# stepper_driver.net
KiCad netlist of a schematic drawn in EAGLE
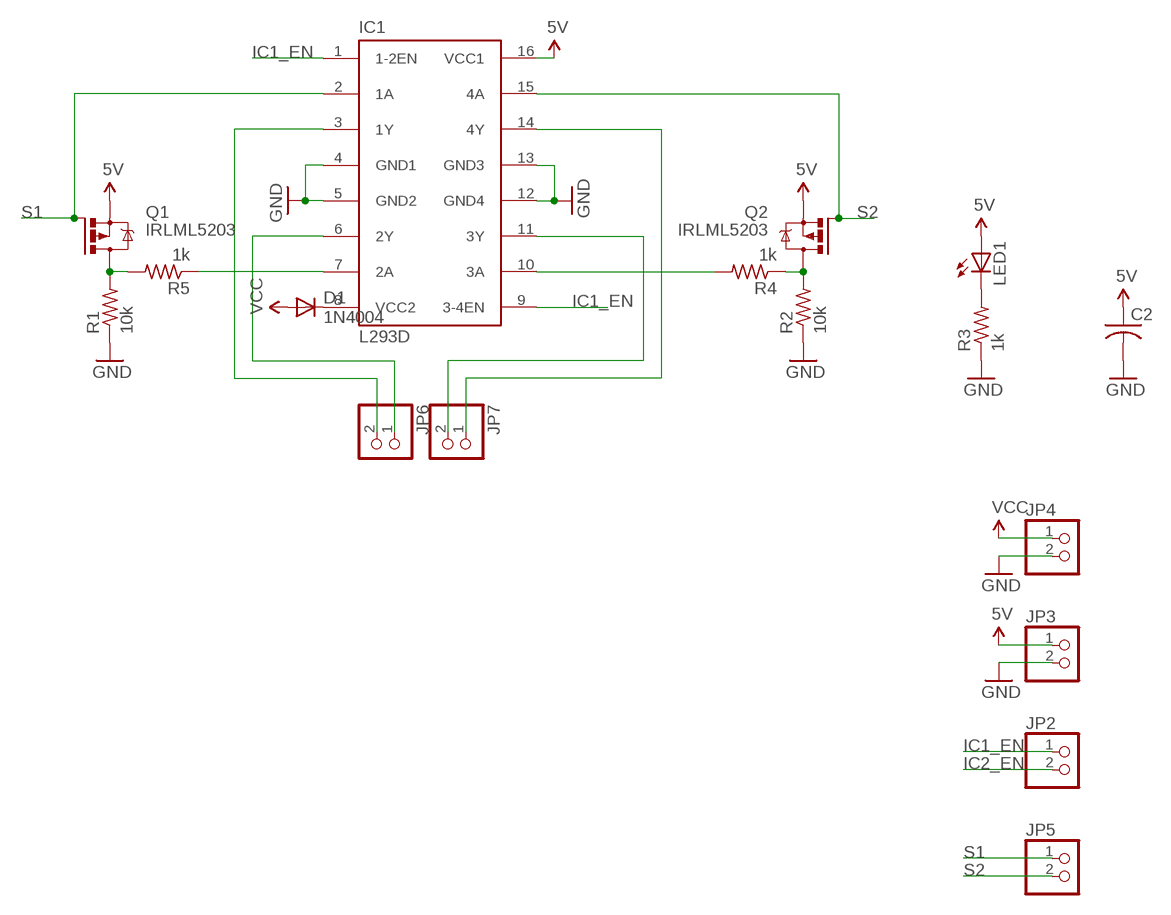
[diagram p0: schematic, sheet 1]

(export (version "E")
  (design (tool "Eeschema 10.0.6"))
  (components
    (comp (ref "C2")
      (value "C-USC1206")
      (footprint "eagle-import:C1206")
      (libsource (lib "eagle-import") (part "C-USC1206"))
    )
    (comp (ref "D1")
      (value "1N4004")
      (footprint "eagle-import:DO41-10")
      (libsource (lib "eagle-import") (part "1N4004"))
    )
    (comp (ref "IC1")
      (value "L293D")
      (footprint "eagle-import:DIL16")
      (libsource (lib "eagle-import") (part "L293D"))
    )
    (comp (ref "JP2")
      (value "PINHD-1X2")
      (footprint "eagle-import:1X02")
      (libsource (lib "eagle-import") (part "PINHD-1X2"))
    )
    (comp (ref "JP3")
      (value "PINHD-1X2")
      (footprint "eagle-import:1X02")
      (libsource (lib "eagle-import") (part "PINHD-1X2"))
    )
    (comp (ref "JP4")
      (value "PINHD-1X2")
      (footprint "eagle-import:1X02")
      (libsource (lib "eagle-import") (part "PINHD-1X2"))
    )
    (comp (ref "JP5")
      (value "PINHD-1X2")
      (footprint "eagle-import:1X02")
      (libsource (lib "eagle-import") (part "PINHD-1X2"))
    )
    (comp (ref "JP6")
      (value "PINHD-1X2")
      (footprint "eagle-import:1X02")
      (libsource (lib "eagle-import") (part "PINHD-1X2"))
    )
    (comp (ref "JP7")
      (value "PINHD-1X2")
      (footprint "eagle-import:1X02")
      (libsource (lib "eagle-import") (part "PINHD-1X2"))
    )
    (comp (ref "LED1")
      (value "LED5MM")
      (footprint "eagle-import:LED5MM")
      (libsource (lib "eagle-import") (part "LED5MM"))
    )
    (comp (ref "Q1")
      (value "IRLML5203")
      (footprint "eagle-import:MICRO3")
      (libsource (lib "eagle-import") (part "IRLML5203"))
    )
    (comp (ref "Q2")
      (value "IRLML5203")
      (footprint "eagle-import:MICRO3")
      (libsource (lib "eagle-import") (part "IRLML5203"))
    )
    (comp (ref "R1")
      (value "10k")
      (footprint "eagle-import:0207_10")
      (libsource (lib "eagle-import") (part "R-US_0207/10"))
    )
    (comp (ref "R2")
      (value "10k")
      (footprint "eagle-import:0207_10")
      (libsource (lib "eagle-import") (part "R-US_0207/10"))
    )
    (comp (ref "R3")
      (value "1k")
      (footprint "eagle-import:0207_10")
      (libsource (lib "eagle-import") (part "R-US_0207/10"))
    )
    (comp (ref "R4")
      (value "1k")
      (footprint "eagle-import:0207_10")
      (libsource (lib "eagle-import") (part "R-US_0207/10"))
    )
    (comp (ref "R5")
      (value "1k")
      (footprint "eagle-import:0207_10")
      (libsource (lib "eagle-import") (part "R-US_0207/10"))
    )
  )
  (nets
    (net (code "1") (name "/IC1_EN") (class "Default")
      (node (ref "IC1") (pin "1") (pinfunction "1-2EN_1") (pintype "input"))
      (node (ref "IC1") (pin "9") (pinfunction "3-4EN_9") (pintype "input"))
      (node (ref "JP2") (pin "1") (pinfunction "1_1") (pintype "passive"))
    )
    (net (code "2") (name "/IC2_EN") (class "Default")
      (node (ref "JP2") (pin "2") (pinfunction "2_2") (pintype "passive"))
    )
    (net (code "3") (name "/S1") (class "Default")
      (node (ref "IC1") (pin "2") (pinfunction "1A_2") (pintype "input"))
      (node (ref "JP5") (pin "1") (pinfunction "1_1") (pintype "passive"))
      (node (ref "Q1") (pin "1") (pinfunction "G_1") (pintype "passive"))
    )
    (net (code "4") (name "/S2") (class "Default")
      (node (ref "IC1") (pin "15") (pinfunction "4A_15") (pintype "input"))
      (node (ref "JP5") (pin "2") (pinfunction "2_2") (pintype "passive"))
      (node (ref "Q2") (pin "1") (pinfunction "G_1") (pintype "passive"))
    )
    (net (code "5") (name "5V") (class "Default")
      (node (ref "C2") (pin "1") (pinfunction "1_1") (pintype "passive"))
      (node (ref "IC1") (pin "16") (pinfunction "VCC1_16") (pintype "power_in"))
      (node (ref "JP3") (pin "1") (pinfunction "1_1") (pintype "passive"))
      (node (ref "LED1") (pin "A") (pinfunction "A_A") (pintype "passive"))
      (node (ref "Q1") (pin "2") (pinfunction "S_2") (pintype "passive"))
      (node (ref "Q2") (pin "2") (pinfunction "S_2") (pintype "passive"))
    )
    (net (code "6") (name "GND") (class "Default")
      (node (ref "C2") (pin "2") (pinfunction "2_2") (pintype "passive"))
      (node (ref "IC1") (pin "12") (pinfunction "GND4_12") (pintype "power_in"))
      (node (ref "IC1") (pin "13") (pinfunction "GND3_13") (pintype "power_in"))
      (node (ref "IC1") (pin "4") (pinfunction "GND1_4") (pintype "power_in"))
      (node (ref "IC1") (pin "5") (pinfunction "GND2_5") (pintype "power_in"))
      (node (ref "JP3") (pin "2") (pinfunction "2_2") (pintype "passive"))
      (node (ref "JP4") (pin "2") (pinfunction "2_2") (pintype "passive"))
      (node (ref "R1") (pin "1") (pinfunction "1_1") (pintype "passive"))
      (node (ref "R2") (pin "1") (pinfunction "1_1") (pintype "passive"))
      (node (ref "R3") (pin "1") (pinfunction "1_1") (pintype "passive"))
    )
    (net (code "7") (name "Net-(IC1-1Y)") (class "Default")
      (node (ref "IC1") (pin "3") (pinfunction "1Y_3") (pintype "output"))
      (node (ref "JP6") (pin "2") (pinfunction "2_2") (pintype "passive"))
    )
    (net (code "8") (name "Net-(IC1-2A)") (class "Default")
      (node (ref "IC1") (pin "7") (pinfunction "2A_7") (pintype "input"))
      (node (ref "R5") (pin "1") (pinfunction "1_1") (pintype "passive"))
    )
    (net (code "9") (name "Net-(IC1-2Y)") (class "Default")
      (node (ref "IC1") (pin "6") (pinfunction "2Y_6") (pintype "output"))
      (node (ref "JP6") (pin "1") (pinfunction "1_1") (pintype "passive"))
    )
    (net (code "10") (name "Net-(IC1-3A)") (class "Default")
      (node (ref "IC1") (pin "10") (pinfunction "3A_10") (pintype "input"))
      (node (ref "R4") (pin "2") (pinfunction "2_2") (pintype "passive"))
    )
    (net (code "11") (name "Net-(IC1-3Y)") (class "Default")
      (node (ref "IC1") (pin "11") (pinfunction "3Y_11") (pintype "output"))
      (node (ref "JP7") (pin "2") (pinfunction "2_2") (pintype "passive"))
    )
    (net (code "12") (name "Net-(IC1-4Y)") (class "Default")
      (node (ref "IC1") (pin "14") (pinfunction "4Y_14") (pintype "output"))
      (node (ref "JP7") (pin "1") (pinfunction "1_1") (pintype "passive"))
    )
    (net (code "13") (name "Net-(IC1-VCC2)") (class "Default")
      (node (ref "D1") (pin "C") (pinfunction "C_C") (pintype "passive"))
      (node (ref "IC1") (pin "8") (pinfunction "VCC2_8") (pintype "power_in"))
    )
    (net (code "14") (name "Net-(LED1-C)") (class "Default")
      (node (ref "LED1") (pin "K") (pinfunction "C_K") (pintype "passive"))
      (node (ref "R3") (pin "2") (pinfunction "2_2") (pintype "passive"))
    )
    (net (code "15") (name "Net-(Q1-D)") (class "Default")
      (node (ref "Q1") (pin "3") (pinfunction "D_3") (pintype "passive"))
      (node (ref "R1") (pin "2") (pinfunction "2_2") (pintype "passive"))
      (node (ref "R5") (pin "2") (pinfunction "2_2") (pintype "passive"))
    )
    (net (code "16") (name "Net-(Q2-D)") (class "Default")
      (node (ref "Q2") (pin "3") (pinfunction "D_3") (pintype "passive"))
      (node (ref "R2") (pin "2") (pinfunction "2_2") (pintype "passive"))
      (node (ref "R4") (pin "1") (pinfunction "1_1") (pintype "passive"))
    )
    (net (code "17") (name "VCC") (class "Default")
      (node (ref "D1") (pin "A") (pinfunction "A_A") (pintype "passive"))
      (node (ref "JP4") (pin "1") (pinfunction "1_1") (pintype "passive"))
    )
  )
)
